# Wifi_Module.net
KiCad netlist of a schematic drawn in Altium Designer
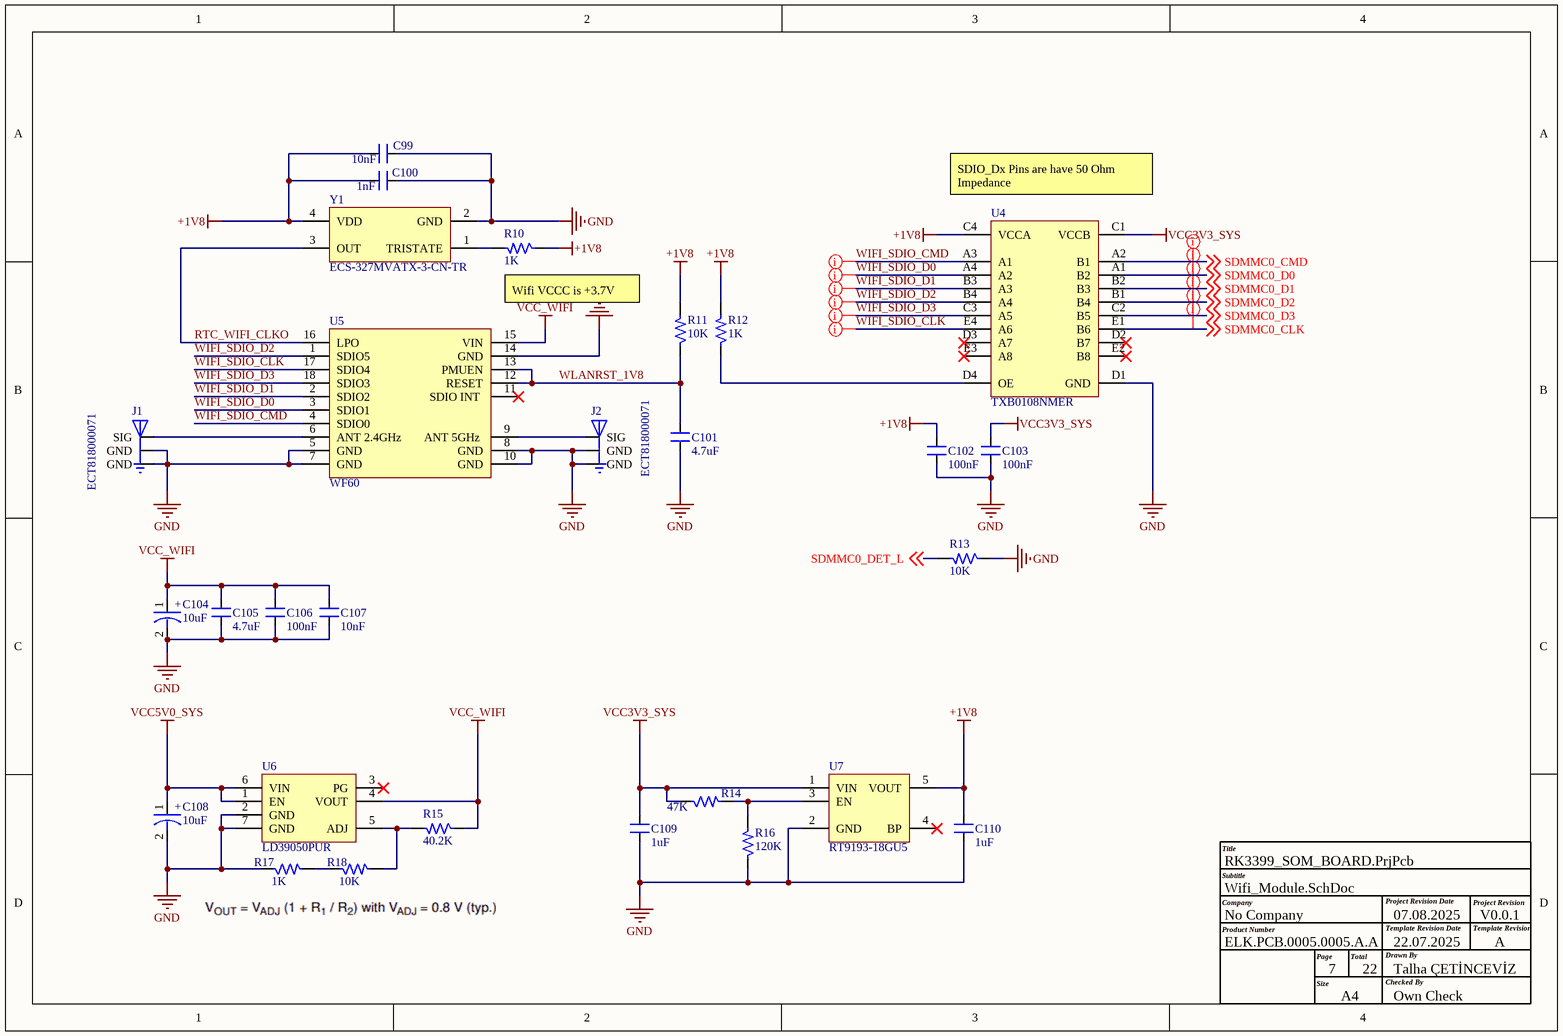
[diagram p0: Wifi_Module.SchDoc]

(export (version "E")
  (design (tool "Eeschema 10.0.6"))
  (components
    (comp (ref "C99")
      (value "10nF")
      (footprint "CAP_0402")
      (description "10000pF ±10% 10V Ceramic Capacitor X7R 0402 (1005 Metric)")
      (fields
        (field (name "MANUFACTURER") "AVX Corporation")
        (field (name "MANUFACTURER PART NUMBER") "0402ZC103KAT2A")
      )
      (libsource (lib "EsteemPCB_SOM_Course_intlib") (part "CAP_10nF-10V-10%-0402"))
    )
    (comp (ref "C100")
      (value "1nF")
      (footprint "CAP_0402")
      (description "1000pF ±10% 16V Ceramic Capacitor X7R 0402 (1005 Metric)")
      (fields
        (field (name "MANUFACTURER") "Yageo")
        (field (name "MANUFACTURER PART NUMBER") "CC0402KRX7R7BB102")
      )
      (libsource (lib "EsteemPCB_SOM_Course_intlib") (part "CAP_1nF-16V-10%-0402"))
    )
    (comp (ref "C101")
      (value "4.7uF")
      (footprint "CAP_0402")
      (description "4.7µF ±10% 10V Ceramic Capacitor X5R 0402 (1005 Metric)")
      (fields
        (field (name "MANUFACTURER") "Samsung Electro-Mechanics")
        (field (name "MANUFACTURER PART NUMBER") "CL05A475KP5NRNC")
      )
      (libsource (lib "EsteemPCB_SOM_Course_intlib") (part "CAP_4.7uF-10V-10%-0402"))
    )
    (comp (ref "C102")
      (value "100nF")
      (footprint "CAP_0201")
      (description "0.1µF ±10% 25V Ceramic Capacitor X5R 0201 (0603 Metric)")
      (fields
        (field (name "MANUFACTURER") "TDK Corporation")
        (field (name "MANUFACTURER PART NUMBER") "C0603X5R1E104K030BB")
      )
      (libsource (lib "EsteemPCB_SOM_Course_intlib") (part "CAP_100nF-25V-10%-0201"))
    )
    (comp (ref "C103")
      (value "100nF")
      (footprint "CAP_0201")
      (description "0.1µF ±10% 25V Ceramic Capacitor X5R 0201 (0603 Metric)")
      (fields
        (field (name "MANUFACTURER") "TDK Corporation")
        (field (name "MANUFACTURER PART NUMBER") "C0603X5R1E104K030BB")
      )
      (libsource (lib "EsteemPCB_SOM_Course_intlib") (part "CAP_100nF-25V-10%-0201"))
    )
    (comp (ref "C104")
      (value "10uF")
      (footprint "CAP-T_1206")
      (description "10µF Molded Tantalum Capacitors 16V 1206 (3216 Metric) 3Ohm")
      (fields
        (field (name "MANUFACTURER") "AVX Corporation")
        (field (name "MANUFACTURER PART NUMBER") "TAJA106K016SNJ")
      )
      (libsource (lib "EsteemPCB_SOM_Course_intlib") (part "CAP-P_10uF-16V-10%-1206"))
    )
    (comp (ref "C105")
      (value "4.7uF")
      (footprint "CAP_0402")
      (description "4.7µF ±10% 10V Ceramic Capacitor X5R 0402 (1005 Metric)")
      (fields
        (field (name "MANUFACTURER") "Samsung Electro-Mechanics")
        (field (name "MANUFACTURER PART NUMBER") "CL05A475KP5NRNC")
      )
      (libsource (lib "EsteemPCB_SOM_Course_intlib") (part "CAP_4.7uF-10V-10%-0402"))
    )
    (comp (ref "C106")
      (value "100nF")
      (footprint "CAP_0201")
      (description "0.1µF ±10% 25V Ceramic Capacitor X5R 0201 (0603 Metric)")
      (fields
        (field (name "MANUFACTURER") "TDK Corporation")
        (field (name "MANUFACTURER PART NUMBER") "C0603X5R1E104K030BB")
      )
      (libsource (lib "EsteemPCB_SOM_Course_intlib") (part "CAP_100nF-25V-10%-0201"))
    )
    (comp (ref "C107")
      (value "10nF")
      (footprint "CAP_0402")
      (description "10000pF ±10% 10V Ceramic Capacitor X7R 0402 (1005 Metric)")
      (fields
        (field (name "MANUFACTURER") "AVX Corporation")
        (field (name "MANUFACTURER PART NUMBER") "0402ZC103KAT2A")
      )
      (libsource (lib "EsteemPCB_SOM_Course_intlib") (part "CAP_10nF-10V-10%-0402"))
    )
    (comp (ref "C108")
      (value "10uF")
      (footprint "CAP-T_1206")
      (description "10µF Molded Tantalum Capacitors 16V 1206 (3216 Metric) 3Ohm")
      (fields
        (field (name "MANUFACTURER") "AVX Corporation")
        (field (name "MANUFACTURER PART NUMBER") "TAJA106K016SNJ")
      )
      (libsource (lib "EsteemPCB_SOM_Course_intlib") (part "CAP-P_10uF-16V-10%-1206"))
    )
    (comp (ref "C109")
      (value "1uF")
      (footprint "CAP_0201")
      (description "1µF ±20% 16V Ceramic Capacitor X5R 0201 (0603 Metric)")
      (fields
        (field (name "MANUFACTURER") "Samsung Electro-Mechanics")
        (field (name "MANUFACTURER PART NUMBER") "CL03A105MO3NRNH")
      )
      (libsource (lib "EsteemPCB_SOM_Course_intlib") (part "CAP_1uF-16V-10%-0201"))
    )
    (comp (ref "C110")
      (value "1uF")
      (footprint "CAP_0201")
      (description "1µF ±20% 16V Ceramic Capacitor X5R 0201 (0603 Metric)")
      (fields
        (field (name "MANUFACTURER") "Samsung Electro-Mechanics")
        (field (name "MANUFACTURER PART NUMBER") "CL03A105MO3NRNH")
      )
      (libsource (lib "EsteemPCB_SOM_Course_intlib") (part "CAP_1uF-16V-10%-0201"))
    )
    (comp (ref "J1")
      (value "ECT818000071")
      (footprint "CON3_UFL_116_SMD_ST")
      (description "SMD RF Connectors/Coaxial Connectors RoHS")
      (fields (field (name "MANUFACTURER") "ECT"))
      (libsource (lib "EsteemPCB_SOM_Course_intlib") (part "CON-PLG_3X1-ECT818000071-ST-SMD"))
    )
    (comp (ref "J2")
      (value "ECT818000071")
      (footprint "CON3_UFL_116_SMD_ST")
      (description "SMD RF Connectors/Coaxial Connectors RoHS")
      (fields (field (name "MANUFACTURER") "ECT"))
      (libsource (lib "EsteemPCB_SOM_Course_intlib") (part "CON-PLG_3X1-ECT818000071-ST-SMD"))
    )
    (comp (ref "R10")
      (value "1K")
      (footprint "RES_0402")
      (description "1 kOhms ±1% 0.1W, 1/10W Chip Resistor 0402 (1005 Metric) Anti-Sulfur Thin Film")
      (fields
        (field (name "MANUFACTURER") "Vishay Beyschlag/Draloric/BC Components")
        (field (name "MANUFACTURER PART NUMBER") "MCS04020C1001FE000")
      )
      (libsource (lib "EsteemPCB_SOM_Course_intlib") (part "RES_1K-0.1W-1%-0402"))
    )
    (comp (ref "R11")
      (value "10K")
      (footprint "RES_0201")
      (description "10 kOhms ±1% 0.05W, 1/20W Chip Resistor 0201 (0603 Metric) Thick Film")
      (fields
        (field (name "MANUFACTURER") "Stackpole Electronics Inc")
        (field (name "MANUFACTURER PART NUMBER") "RMCF0201FT10K0")
      )
      (libsource (lib "EsteemPCB_SOM_Course_intlib") (part "RES_10K-0.05W-1%-0201"))
    )
    (comp (ref "R12")
      (value "1K")
      (footprint "RES_0402")
      (description "1 kOhms ±1% 0.1W, 1/10W Chip Resistor 0402 (1005 Metric) Anti-Sulfur Thin Film")
      (fields
        (field (name "MANUFACTURER") "Vishay Beyschlag/Draloric/BC Components")
        (field (name "MANUFACTURER PART NUMBER") "MCS04020C1001FE000")
      )
      (libsource (lib "EsteemPCB_SOM_Course_intlib") (part "RES_1K-0.1W-1%-0402"))
    )
    (comp (ref "R13")
      (value "10K")
      (footprint "RES_0201")
      (description "10 kOhms ±1% 0.05W, 1/20W Chip Resistor 0201 (0603 Metric) Thick Film")
      (fields
        (field (name "MANUFACTURER") "Stackpole Electronics Inc")
        (field (name "MANUFACTURER PART NUMBER") "RMCF0201FT10K0")
      )
      (libsource (lib "EsteemPCB_SOM_Course_intlib") (part "RES_10K-0.05W-1%-0201"))
    )
    (comp (ref "R14")
      (value "47K")
      (footprint "RES_0402")
      (description "47 kOhms ±1% 0.1W, 1/10W Chip Resistor 0402 (1005 Metric) Automotive AEC-Q200 Thick Film")
      (fields
        (field (name "MANUFACTURER") "Panasonic Electronic Components")
        (field (name "MANUFACTURER PART NUMBER") "ERJ-2RKF4702X")
      )
      (libsource (lib "EsteemPCB_SOM_Course_intlib") (part "RES_47K-0.1W-1%-0402"))
    )
    (comp (ref "R15")
      (value "40.2K")
      (footprint "RES_0201")
      (fields
        (field (name "MANUFACTURER") "Yageo")
        (field (name "MANUFACTURER PART NUMBER") "AC0201FR-0740K2L")
      )
      (libsource (lib "EsteemPCB_SOM_Course_intlib") (part "RES_40.2K-0.05W-1%-0201"))
    )
    (comp (ref "R16")
      (value "120K")
      (footprint "RES_0402")
      (description "120 kOhms ±1% 0.1W, 1/10W Chip Resistor 0402 (1005 Metric) Anti-Sulfur Thin Film")
      (fields
        (field (name "MANUFACTURER") "Vishay Beyschlag/Draloric/BC Components")
        (field (name "MANUFACTURER PART NUMBER") "MCS04020C1203FE000")
      )
      (libsource (lib "EsteemPCB_SOM_Course_intlib") (part "RES_120K-0.1W-1%-0402"))
    )
    (comp (ref "R17")
      (value "1K")
      (footprint "RES_0201")
      (description "1 kOhms ±1% 0.05W, 1/20W Chip Resistor 0201 (0603 Metric) Thick Film")
      (fields
        (field (name "MANUFACTURER") "Yageo")
        (field (name "MANUFACTURER PART NUMBER") "RC0201FR-071KL")
      )
      (libsource (lib "EsteemPCB_SOM_Course_intlib") (part "RES_1K-0.05W-1%-0201"))
    )
    (comp (ref "R18")
      (value "10K")
      (footprint "RES_0201")
      (description "10 kOhms ±1% 0.05W, 1/20W Chip Resistor 0201 (0603 Metric) Thick Film")
      (fields
        (field (name "MANUFACTURER") "Stackpole Electronics Inc")
        (field (name "MANUFACTURER PART NUMBER") "RMCF0201FT10K0")
      )
      (libsource (lib "EsteemPCB_SOM_Course_intlib") (part "RES_10K-0.05W-1%-0201"))
    )
    (comp (ref "U4")
      (value "TXB0108NMER")
      (footprint "NFBGA_31.4_125.9X102.36")
      (fields (field (name "MANUFACTURER") "Texas Instruments"))
      (libsource (lib "EsteemPCB_SOM_Course_intlib") (part "IC_TXB0108NMER"))
    )
    (comp (ref "U5")
      (value "WF60")
      (footprint "MOD_WF60")
      (description "Amp’ed RF Tech presents the WF60 WiFi dual\r\nband module: 802.11abgn.")
      (fields (field (name "MANUFACTURER") "Amp’ed"))
      (libsource (lib "EsteemPCB_SOM_Course_intlib") (part "MOD_WF60-SMD"))
    )
    (comp (ref "U6")
      (value "LD39050PUR")
      (footprint "DFN-6_37.4_165_33X15_SMD")
      (description "Adjustable 5.5V 0.8V 500mA DFN-6 Linear Voltage Regulators RoHS")
      (fields (field (name "MANUFACTURER") "STMicroelectronics"))
      (libsource (lib "EsteemPCB_SOM_Course_intlib") (part "REG_5.5V-0~5.1V-0.5A-2.55W-DFN-6"))
    )
    (comp (ref "U7")
      (value "RT9193-18GU5")
      (footprint "SC70-5")
      (description "Linear Voltage Regulator IC 1 Output 300mA SC-70-5")
      (fields (field (name "MANUFACTURER") "Richtek USA Inc."))
      (libsource (lib "EsteemPCB_SOM_Course_intlib") (part "REG_1.8V-300mA-5.5V-SC70-5"))
    )
    (comp (ref "Y1")
      (value "ECS-327MVATX-3-CN-TR")
      (footprint "XTAL_57_35X31_SMD")
      (description "32.768kHz XO (Standard) CMOS Oscillator 1.6V ~ 3.6V Enable/Disable 4-SMD, No Lead")
      (fields (field (name "MANUFACTURER") "ECS INC"))
      (libsource (lib "EsteemPCB_SOM_Course_intlib") (part "XTAL_ECS-327MVATX-2-CN-TR"))
    )
  )
  (nets
    (net (code "1") (name "+1V8") (class "Default")
      (node (ref "C100") (pin "1") (pinfunction "1_1") (pintype "passive"))
      (node (ref "C102") (pin "1") (pinfunction "1_1") (pintype "passive"))
      (node (ref "C110") (pin "2") (pinfunction "2_2") (pintype "passive"))
      (node (ref "C99") (pin "1") (pinfunction "1_1") (pintype "passive"))
      (node (ref "R10") (pin "1") (pinfunction "1_1") (pintype "passive"))
      (node (ref "R11") (pin "2") (pinfunction "2_2") (pintype "passive"))
      (node (ref "R12") (pin "2") (pinfunction "2_2") (pintype "passive"))
      (node (ref "U4") (pin "C4") (pinfunction "VCCA_C4") (pintype "passive"))
      (node (ref "U7") (pin "5") (pinfunction "VOUT_5") (pintype "passive"))
      (node (ref "Y1") (pin "4") (pinfunction "VDD_4") (pintype "passive"))
    )
    (net (code "2") (name "/RTC_WIFI_CLKO") (class "Default")
      (node (ref "U5") (pin "16") (pinfunction "LPO_16") (pintype "passive"))
      (node (ref "Y1") (pin "3") (pinfunction "OUT_3") (pintype "passive"))
    )
    (net (code "3") (name "/WIFI_SDIO_CLK") (class "Default")
      (node (ref "U4") (pin "E4") (pinfunction "A6_E4") (pintype "passive"))
      (node (ref "U5") (pin "17") (pinfunction "SDIO4_17") (pintype "passive"))
    )
    (net (code "4") (name "/WIFI_SDIO_CMD") (class "Default")
      (node (ref "U4") (pin "A3") (pinfunction "A1_A3") (pintype "passive"))
      (node (ref "U5") (pin "4") (pinfunction "SDIO0_4") (pintype "passive"))
    )
    (net (code "5") (name "/WIFI_SDIO_D0") (class "Default")
      (node (ref "U4") (pin "A4") (pinfunction "A2_A4") (pintype "passive"))
      (node (ref "U5") (pin "3") (pinfunction "SDIO1_3") (pintype "passive"))
    )
    (net (code "6") (name "/WIFI_SDIO_D1") (class "Default")
      (node (ref "U4") (pin "B3") (pinfunction "A3_B3") (pintype "passive"))
      (node (ref "U5") (pin "2") (pinfunction "SDIO2_2") (pintype "passive"))
    )
    (net (code "7") (name "/WIFI_SDIO_D2") (class "Default")
      (node (ref "U4") (pin "B4") (pinfunction "A4_B4") (pintype "passive"))
      (node (ref "U5") (pin "1") (pinfunction "SDIO5_1") (pintype "passive"))
    )
    (net (code "8") (name "/WIFI_SDIO_D3") (class "Default")
      (node (ref "U4") (pin "C3") (pinfunction "A5_C3") (pintype "passive"))
      (node (ref "U5") (pin "18") (pinfunction "SDIO3_18") (pintype "passive"))
    )
    (net (code "9") (name "/WLANRST_1V8") (class "Default")
      (node (ref "C101") (pin "2") (pinfunction "2_2") (pintype "passive"))
      (node (ref "R11") (pin "1") (pinfunction "1_1") (pintype "passive"))
      (node (ref "U5") (pin "12") (pinfunction "RESET_12") (pintype "passive"))
      (node (ref "U5") (pin "13") (pinfunction "PMUEN_13") (pintype "passive"))
    )
    (net (code "10") (name "GND") (class "Default")
      (node (ref "C100") (pin "2") (pinfunction "2_2") (pintype "passive"))
      (node (ref "C101") (pin "1") (pinfunction "1_1") (pintype "passive"))
      (node (ref "C102") (pin "2") (pinfunction "2_2") (pintype "passive"))
      (node (ref "C103") (pin "2") (pinfunction "2_2") (pintype "passive"))
      (node (ref "C104") (pin "2") (pinfunction "2_2") (pintype "passive"))
      (node (ref "C105") (pin "1") (pinfunction "1_1") (pintype "passive"))
      (node (ref "C106") (pin "1") (pinfunction "1_1") (pintype "passive"))
      (node (ref "C107") (pin "1") (pinfunction "1_1") (pintype "passive"))
      (node (ref "C108") (pin "2") (pinfunction "2_2") (pintype "passive"))
      (node (ref "C109") (pin "1") (pinfunction "1_1") (pintype "passive"))
      (node (ref "C110") (pin "1") (pinfunction "1_1") (pintype "passive"))
      (node (ref "C99") (pin "2") (pinfunction "2_2") (pintype "passive"))
      (node (ref "J1") (pin "1") (pinfunction "GND_1") (pintype "passive"))
      (node (ref "J1") (pin "3") (pinfunction "GND_3") (pintype "passive"))
      (node (ref "J2") (pin "1") (pinfunction "GND_1") (pintype "passive"))
      (node (ref "J2") (pin "3") (pinfunction "GND_3") (pintype "passive"))
      (node (ref "R13") (pin "1") (pinfunction "1_1") (pintype "passive"))
      (node (ref "R16") (pin "1") (pinfunction "1_1") (pintype "passive"))
      (node (ref "R17") (pin "1") (pinfunction "1_1") (pintype "passive"))
      (node (ref "U4") (pin "D1") (pinfunction "GND_D1") (pintype "passive"))
      (node (ref "U5") (pin "10") (pinfunction "GND_10") (pintype "passive"))
      (node (ref "U5") (pin "14") (pinfunction "GND_14") (pintype "passive"))
      (node (ref "U5") (pin "5") (pinfunction "GND_5") (pintype "passive"))
      (node (ref "U5") (pin "7") (pinfunction "GND_7") (pintype "passive"))
      (node (ref "U5") (pin "8") (pinfunction "GND_8") (pintype "passive"))
      (node (ref "U6") (pin "2") (pinfunction "GND_2") (pintype "passive"))
      (node (ref "U6") (pin "7") (pinfunction "GND_7") (pintype "passive"))
      (node (ref "U7") (pin "2") (pinfunction "GND_2") (pintype "passive"))
      (node (ref "Y1") (pin "2") (pinfunction "GND_2") (pintype "passive"))
    )
    (net (code "11") (name "Net-(J1-SIG)") (class "Default")
      (node (ref "J1") (pin "2") (pinfunction "SIG_2") (pintype "passive"))
      (node (ref "U5") (pin "6") (pinfunction "ANT_2.4GHz_6") (pintype "passive"))
    )
    (net (code "12") (name "Net-(J2-SIG)") (class "Default")
      (node (ref "J2") (pin "2") (pinfunction "SIG_2") (pintype "passive"))
      (node (ref "U5") (pin "9") (pinfunction "ANT_5GHz_9") (pintype "passive"))
    )
    (net (code "13") (name "Net-(R17-Pad2)") (class "Default")
      (node (ref "R17") (pin "2") (pinfunction "2_2") (pintype "passive"))
      (node (ref "R18") (pin "1") (pinfunction "1_1") (pintype "passive"))
    )
    (net (code "14") (name "Net-(U4-OE)") (class "Default")
      (node (ref "R12") (pin "1") (pinfunction "1_1") (pintype "passive"))
      (node (ref "U4") (pin "D4") (pinfunction "OE_D4") (pintype "passive"))
    )
    (net (code "15") (name "Net-(U6-ADJ)") (class "Default")
      (node (ref "R15") (pin "2") (pinfunction "2_2") (pintype "passive"))
      (node (ref "R18") (pin "2") (pinfunction "2_2") (pintype "passive"))
      (node (ref "U6") (pin "5") (pinfunction "ADJ_5") (pintype "passive"))
    )
    (net (code "16") (name "Net-(U7-EN)") (class "Default")
      (node (ref "R14") (pin "2") (pinfunction "2_2") (pintype "passive"))
      (node (ref "R16") (pin "2") (pinfunction "2_2") (pintype "passive"))
      (node (ref "U7") (pin "3") (pinfunction "EN_3") (pintype "passive"))
    )
    (net (code "17") (name "Net-(Y1-TRISTATE)") (class "Default")
      (node (ref "R10") (pin "2") (pinfunction "2_2") (pintype "passive"))
      (node (ref "Y1") (pin "1") (pinfunction "TRISTATE_1") (pintype "passive"))
    )
    (net (code "18") (name "SDMMC0_CLK") (class "Default")
      (node (ref "U4") (pin "E1") (pinfunction "B6_E1") (pintype "passive"))
    )
    (net (code "19") (name "SDMMC0_CMD") (class "Default")
      (node (ref "U4") (pin "A2") (pinfunction "B1_A2") (pintype "passive"))
    )
    (net (code "20") (name "SDMMC0_D0") (class "Default")
      (node (ref "U4") (pin "A1") (pinfunction "B2_A1") (pintype "passive"))
    )
    (net (code "21") (name "SDMMC0_D1") (class "Default")
      (node (ref "U4") (pin "B2") (pinfunction "B3_B2") (pintype "passive"))
    )
    (net (code "22") (name "SDMMC0_D2") (class "Default")
      (node (ref "U4") (pin "B1") (pinfunction "B4_B1") (pintype "passive"))
    )
    (net (code "23") (name "SDMMC0_D3") (class "Default")
      (node (ref "U4") (pin "C2") (pinfunction "B5_C2") (pintype "passive"))
    )
    (net (code "24") (name "SDMMC0_DET_L") (class "Default")
      (node (ref "R13") (pin "2") (pinfunction "2_2") (pintype "passive"))
    )
    (net (code "25") (name "VCC3V3_SYS") (class "Default")
      (node (ref "C103") (pin "1") (pinfunction "1_1") (pintype "passive"))
      (node (ref "C109") (pin "2") (pinfunction "2_2") (pintype "passive"))
      (node (ref "R14") (pin "1") (pinfunction "1_1") (pintype "passive"))
      (node (ref "U4") (pin "C1") (pinfunction "VCCB_C1") (pintype "passive"))
      (node (ref "U7") (pin "1") (pinfunction "VIN_1") (pintype "passive"))
    )
    (net (code "26") (name "VCC5V0_SYS") (class "Default")
      (node (ref "C108") (pin "1") (pinfunction "1_1") (pintype "passive"))
      (node (ref "U6") (pin "1") (pinfunction "EN_1") (pintype "passive"))
      (node (ref "U6") (pin "6") (pinfunction "VIN_6") (pintype "passive"))
    )
    (net (code "27") (name "VCC_WIFI") (class "Default")
      (node (ref "C104") (pin "1") (pinfunction "1_1") (pintype "passive"))
      (node (ref "C105") (pin "2") (pinfunction "2_2") (pintype "passive"))
      (node (ref "C106") (pin "2") (pinfunction "2_2") (pintype "passive"))
      (node (ref "C107") (pin "2") (pinfunction "2_2") (pintype "passive"))
      (node (ref "R15") (pin "1") (pinfunction "1_1") (pintype "passive"))
      (node (ref "U5") (pin "15") (pinfunction "VIN_15") (pintype "passive"))
      (node (ref "U6") (pin "4") (pinfunction "VOUT_4") (pintype "passive"))
    )
    (net (code "28") (name "unconnected-(U4-A7-PadD3)") (class "Default")
      (node (ref "U4") (pin "D3") (pinfunction "A7_D3") (pintype "passive+no_connect"))
    )
    (net (code "29") (name "unconnected-(U4-A8-PadE3)") (class "Default")
      (node (ref "U4") (pin "E3") (pinfunction "A8_E3") (pintype "passive+no_connect"))
    )
    (net (code "30") (name "unconnected-(U4-B7-PadD2)") (class "Default")
      (node (ref "U4") (pin "D2") (pinfunction "B7_D2") (pintype "passive+no_connect"))
    )
    (net (code "31") (name "unconnected-(U4-B8-PadE2)") (class "Default")
      (node (ref "U4") (pin "E2") (pinfunction "B8_E2") (pintype "passive+no_connect"))
    )
    (net (code "32") (name "unconnected-(U5-SDIO_INT-Pad11)") (class "Default")
      (node (ref "U5") (pin "11") (pinfunction "SDIO_INT_11") (pintype "passive+no_connect"))
    )
    (net (code "33") (name "unconnected-(U6-PG-Pad3)") (class "Default")
      (node (ref "U6") (pin "3") (pinfunction "PG_3") (pintype "passive+no_connect"))
    )
    (net (code "34") (name "unconnected-(U7-BP-Pad4)") (class "Default")
      (node (ref "U7") (pin "4") (pinfunction "BP_4") (pintype "passive+no_connect"))
    )
  )
)
